# Sheet_Shield.net
KiCad netlist of a schematic drawn in Altium Designer
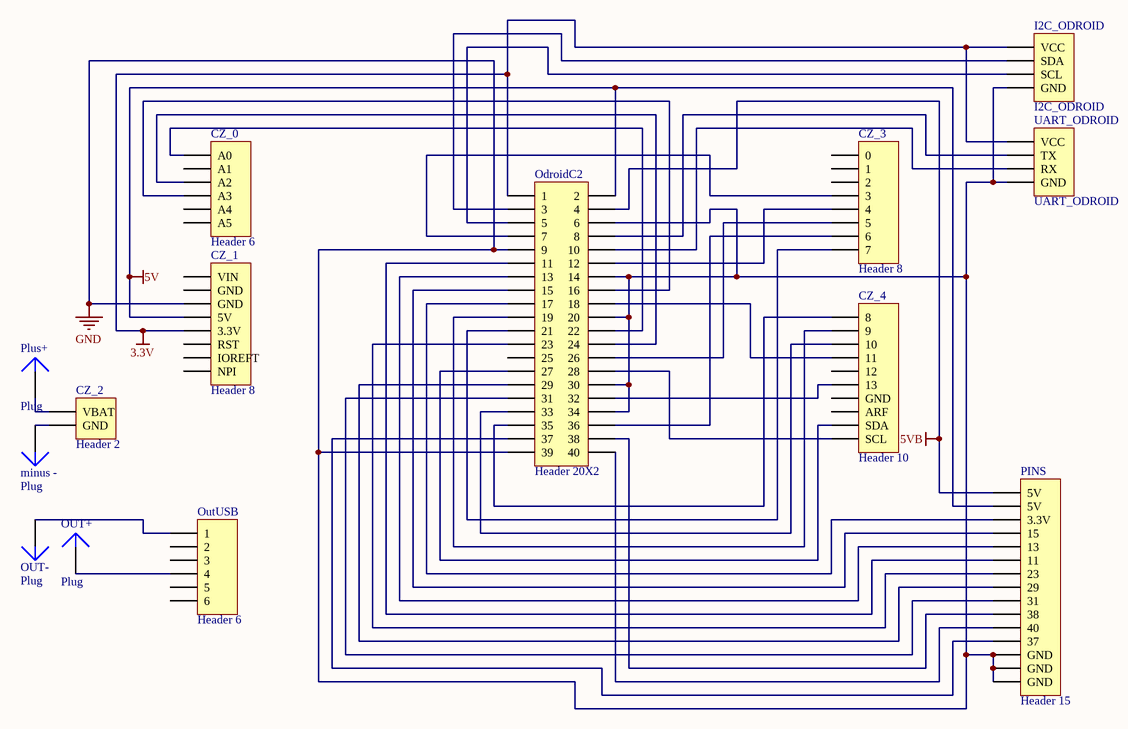
[diagram p0: Sheet_Shield.SchDoc]

(export (version "E")
  (design (tool "Eeschema 10.0.6"))
  (components
    (comp (ref "CZ_0")
      (value "Header 6")
      (footprint "HDR1X6")
      (description "Header, 6-Pin")
      (fields (field (name "PUBLISHER") "Altium Limited"))
      (libsource (lib "Miscellaneous Connectors") (part "Header 6"))
    )
    (comp (ref "CZ_1")
      (value "Header 8")
      (footprint "HDR1X8")
      (description "Header, 8-Pin")
      (fields (field (name "PUBLISHER") "Altium Limited"))
      (libsource (lib "Miscellaneous Connectors") (part "Header 8"))
    )
    (comp (ref "CZ_2")
      (value "Header 2")
      (footprint "HDR1X2")
      (description "Header, 2-Pin")
      (fields (field (name "PUBLISHER") "Altium Limited"))
      (libsource (lib "Miscellaneous Connectors") (part "Header 2"))
    )
    (comp (ref "CZ_3")
      (value "Header 8")
      (footprint "HDR1X8")
      (description "Header, 8-Pin")
      (fields (field (name "PUBLISHER") "Altium Limited"))
      (libsource (lib "Miscellaneous Connectors") (part "Header 8"))
    )
    (comp (ref "CZ_4")
      (value "Header 10")
      (footprint "HDR1X10")
      (description "Header, 10-Pin")
      (fields (field (name "PUBLISHER") "Altium Limited"))
      (libsource (lib "Miscellaneous Connectors") (part "Header 10"))
    )
    (comp (ref "I2C_ODROID")
      (value "I2C_ODROID")
      (footprint "HDR1X4")
      (description "Header, 4-Pin")
      (fields (field (name "PUBLISHER") "Altium Limited"))
      (libsource (lib "Miscellaneous Connectors") (part "Header 4"))
    )
    (comp (ref "minus -")
      (value "Plug")
      (footprint "PIN1")
      (fields (field (name "PUBLISHER") "Altium Limited"))
      (libsource (lib "Miscellaneous Connectors") (part "Plug"))
    )
    (comp (ref "OdroidC2")
      (value "Header 20X2")
      (footprint "HDR2X20")
      (description "Header, 20-Pin, Dual row")
      (fields (field (name "PUBLISHER") "Altium Limited"))
      (libsource (lib "Miscellaneous Connectors") (part "Header 20X2"))
    )
    (comp (ref "OUT+")
      (value "Plug")
      (footprint "PIN1")
      (fields (field (name "PUBLISHER") "Altium Limited"))
      (libsource (lib "Miscellaneous Connectors") (part "Plug"))
    )
    (comp (ref "OUT-")
      (value "Plug")
      (footprint "PIN1")
      (fields (field (name "PUBLISHER") "Altium Limited"))
      (libsource (lib "Miscellaneous Connectors") (part "Plug"))
    )
    (comp (ref "OutUSB")
      (value "Header 6")
      (footprint "USB2.5-2H4C")
      (description "Header, 6-Pin")
      (fields (field (name "PUBLISHER") "Altium Limited"))
      (libsource (lib "") (part "Header 6_1"))
    )
    (comp (ref "PINS")
      (value "Header 15")
      (footprint "HDR1X15")
      (description "Header, 15-Pin")
      (fields (field (name "PUBLISHER") "Altium Limited"))
      (libsource (lib "Miscellaneous Connectors") (part "Header 15"))
    )
    (comp (ref "Plus+")
      (value "Plug")
      (footprint "PIN1")
      (fields (field (name "PUBLISHER") "Altium Limited"))
      (libsource (lib "Miscellaneous Connectors") (part "Plug"))
    )
    (comp (ref "UART_ODROID")
      (value "UART_ODROID")
      (footprint "HDR1X4")
      (description "Header, 4-Pin")
      (fields (field (name "PUBLISHER") "Altium Limited"))
      (libsource (lib "Miscellaneous Connectors") (part "Header 4"))
    )
  )
  (nets
    (net (code "1") (name "3.3V") (class "Default")
      (node (ref "CZ_1") (pin "5") (pinfunction "3.3V_5") (pintype "passive"))
      (node (ref "I2C_ODROID") (pin "1") (pinfunction "VCC_1") (pintype "passive"))
      (node (ref "OdroidC2") (pin "1") (pinfunction "1_1") (pintype "passive"))
      (node (ref "UART_ODROID") (pin "1") (pinfunction "VCC_1") (pintype "passive"))
    )
    (net (code "2") (name "5V") (class "Default")
      (node (ref "CZ_1") (pin "4") (pinfunction "5V_4") (pintype "passive"))
      (node (ref "OdroidC2") (pin "2") (pinfunction "2_2") (pintype "passive"))
      (node (ref "PINS") (pin "2") (pinfunction "5V_2") (pintype "passive"))
    )
    (net (code "3") (name "5VB") (class "Default")
      (node (ref "OdroidC2") (pin "4") (pinfunction "4_4") (pintype "passive"))
      (node (ref "PINS") (pin "1") (pinfunction "5V_1") (pintype "passive"))
    )
    (net (code "4") (name "GND") (class "Default")
      (node (ref "CZ_1") (pin "3") (pinfunction "GND_3") (pintype "passive"))
      (node (ref "I2C_ODROID") (pin "4") (pinfunction "GND_4") (pintype "passive"))
      (node (ref "OdroidC2") (pin "14") (pinfunction "14_14") (pintype "passive"))
      (node (ref "OdroidC2") (pin "20") (pinfunction "20_20") (pintype "passive"))
      (node (ref "OdroidC2") (pin "30") (pinfunction "30_30") (pintype "passive"))
      (node (ref "OdroidC2") (pin "34") (pinfunction "34_34") (pintype "passive"))
      (node (ref "OdroidC2") (pin "39") (pinfunction "39_39") (pintype "passive"))
      (node (ref "OdroidC2") (pin "6") (pinfunction "6_6") (pintype "passive"))
      (node (ref "OdroidC2") (pin "9") (pinfunction "9_9") (pintype "passive"))
      (node (ref "PINS") (pin "13") (pinfunction "GND_13") (pintype "passive"))
      (node (ref "PINS") (pin "14") (pinfunction "GND_14") (pintype "passive"))
      (node (ref "PINS") (pin "15") (pinfunction "GND_15") (pintype "passive"))
      (node (ref "UART_ODROID") (pin "4") (pinfunction "GND_4") (pintype "passive"))
    )
    (net (code "5") (name "Net-(CZ_0-A0)") (class "Default")
      (node (ref "CZ_0") (pin "1") (pinfunction "A0_1") (pintype "passive"))
      (node (ref "OdroidC2") (pin "22") (pinfunction "22_22") (pintype "passive"))
    )
    (net (code "6") (name "Net-(CZ_0-A2)") (class "Default")
      (node (ref "CZ_0") (pin "3") (pinfunction "A2_3") (pintype "passive"))
      (node (ref "OdroidC2") (pin "24") (pinfunction "24_24") (pintype "passive"))
    )
    (net (code "7") (name "Net-(CZ_0-A3)") (class "Default")
      (node (ref "CZ_0") (pin "4") (pinfunction "A3_4") (pintype "passive"))
      (node (ref "OdroidC2") (pin "16") (pinfunction "16_16") (pintype "passive"))
    )
    (net (code "8") (name "Net-(CZ_2-GND)") (class "Default")
      (node (ref "CZ_2") (pin "2") (pinfunction "GND_2") (pintype "passive"))
      (node (ref "minus -") (pin "1") (pinfunction "1_1") (pintype "passive"))
    )
    (net (code "9") (name "Net-(CZ_2-VBAT)") (class "Default")
      (node (ref "CZ_2") (pin "1") (pinfunction "VBAT_1") (pintype "passive"))
      (node (ref "Plus+") (pin "1") (pinfunction "1_1") (pintype "passive"))
    )
    (net (code "10") (name "Net-(CZ_3-3.3V)") (class "Default")
      (node (ref "CZ_3") (pin "5") (pinfunction "3.3V_5") (pintype "passive"))
      (node (ref "OdroidC2") (pin "12") (pinfunction "12_12") (pintype "passive"))
    )
    (net (code "11") (name "Net-(CZ_3-5V)") (class "Default")
      (node (ref "CZ_3") (pin "4") (pinfunction "5V_4") (pintype "passive"))
      (node (ref "OdroidC2") (pin "7") (pinfunction "7_7") (pintype "passive"))
    )
    (net (code "12") (name "Net-(CZ_3-IOREFT)") (class "Default")
      (node (ref "CZ_3") (pin "7") (pinfunction "IOREFT_7") (pintype "passive"))
      (node (ref "OdroidC2") (pin "36") (pinfunction "36_36") (pintype "passive"))
    )
    (net (code "13") (name "Net-(CZ_3-NPI)") (class "Default")
      (node (ref "CZ_3") (pin "8") (pinfunction "NPI_8") (pintype "passive"))
      (node (ref "OdroidC2") (pin "21") (pinfunction "21_21") (pintype "passive"))
    )
    (net (code "14") (name "Net-(CZ_3-RST)") (class "Default")
      (node (ref "CZ_3") (pin "6") (pinfunction "RST_6") (pintype "passive"))
      (node (ref "OdroidC2") (pin "26") (pinfunction "26_26") (pintype "passive"))
    )
    (net (code "15") (name "Net-(CZ_4-8)") (class "Default")
      (node (ref "CZ_4") (pin "1") (pinfunction "8_1") (pintype "passive"))
      (node (ref "OdroidC2") (pin "35") (pinfunction "35_35") (pintype "passive"))
    )
    (net (code "16") (name "Net-(CZ_4-9)") (class "Default")
      (node (ref "CZ_4") (pin "2") (pinfunction "9_2") (pintype "passive"))
      (node (ref "OdroidC2") (pin "19") (pinfunction "19_19") (pintype "passive"))
    )
    (net (code "17") (name "Net-(CZ_4-10)") (class "Default")
      (node (ref "CZ_4") (pin "3") (pinfunction "10_3") (pintype "passive"))
      (node (ref "OdroidC2") (pin "33") (pinfunction "33_33") (pintype "passive"))
    )
    (net (code "18") (name "Net-(CZ_4-11)") (class "Default")
      (node (ref "CZ_4") (pin "4") (pinfunction "11_4") (pintype "passive"))
      (node (ref "OdroidC2") (pin "18") (pinfunction "18_18") (pintype "passive"))
    )
    (net (code "19") (name "Net-(CZ_4-13)") (class "Default")
      (node (ref "CZ_4") (pin "6") (pinfunction "13_6") (pintype "passive"))
      (node (ref "OdroidC2") (pin "32") (pinfunction "32_32") (pintype "passive"))
    )
    (net (code "20") (name "Net-(CZ_4-SCL)") (class "Default")
      (node (ref "CZ_4") (pin "10") (pinfunction "SCL_10") (pintype "passive"))
      (node (ref "OdroidC2") (pin "28") (pinfunction "28_28") (pintype "passive"))
    )
    (net (code "21") (name "Net-(CZ_4-SDA)") (class "Default")
      (node (ref "CZ_4") (pin "9") (pinfunction "SDA_9") (pintype "passive"))
      (node (ref "OdroidC2") (pin "27") (pinfunction "27_27") (pintype "passive"))
    )
    (net (code "22") (name "Net-(I2C_ODROID-SCL)") (class "Default")
      (node (ref "I2C_ODROID") (pin "3") (pinfunction "SCL_3") (pintype "passive"))
      (node (ref "OdroidC2") (pin "5") (pinfunction "5_5") (pintype "passive"))
    )
    (net (code "23") (name "Net-(I2C_ODROID-SDA)") (class "Default")
      (node (ref "I2C_ODROID") (pin "2") (pinfunction "SDA_2") (pintype "passive"))
      (node (ref "OdroidC2") (pin "3") (pinfunction "3_3") (pintype "passive"))
    )
    (net (code "24") (name "Net-(OUT+-Pad1)") (class "Default")
      (node (ref "OUT+") (pin "1") (pinfunction "1_1") (pintype "passive"))
      (node (ref "OutUSB") (pin "4") (pinfunction "4_4") (pintype "passive"))
    )
    (net (code "25") (name "Net-(OUT--Pad1)") (class "Default")
      (node (ref "OUT-") (pin "1") (pinfunction "1_1") (pintype "passive"))
      (node (ref "OutUSB") (pin "1") (pinfunction "1_1") (pintype "passive"))
    )
    (net (code "26") (name "Net-(PINS-3.3V)") (class "Default")
      (node (ref "OdroidC2") (pin "17") (pinfunction "17_17") (pintype "passive"))
      (node (ref "PINS") (pin "3") (pinfunction "3.3V_3") (pintype "passive"))
    )
    (net (code "27") (name "Net-(PINS-11)") (class "Default")
      (node (ref "OdroidC2") (pin "11") (pinfunction "11_11") (pintype "passive"))
      (node (ref "PINS") (pin "6") (pinfunction "11_6") (pintype "passive"))
    )
    (net (code "28") (name "Net-(PINS-13)") (class "Default")
      (node (ref "OdroidC2") (pin "13") (pinfunction "13_13") (pintype "passive"))
      (node (ref "PINS") (pin "5") (pinfunction "13_5") (pintype "passive"))
    )
    (net (code "29") (name "Net-(PINS-15)") (class "Default")
      (node (ref "OdroidC2") (pin "15") (pinfunction "15_15") (pintype "passive"))
      (node (ref "PINS") (pin "4") (pinfunction "15_4") (pintype "passive"))
    )
    (net (code "30") (name "Net-(PINS-23)") (class "Default")
      (node (ref "OdroidC2") (pin "23") (pinfunction "23_23") (pintype "passive"))
      (node (ref "PINS") (pin "7") (pinfunction "23_7") (pintype "passive"))
    )
    (net (code "31") (name "Net-(PINS-29)") (class "Default")
      (node (ref "OdroidC2") (pin "29") (pinfunction "29_29") (pintype "passive"))
      (node (ref "PINS") (pin "8") (pinfunction "29_8") (pintype "passive"))
    )
    (net (code "32") (name "Net-(PINS-31)") (class "Default")
      (node (ref "OdroidC2") (pin "31") (pinfunction "31_31") (pintype "passive"))
      (node (ref "PINS") (pin "9") (pinfunction "31_9") (pintype "passive"))
    )
    (net (code "33") (name "Net-(PINS-37)") (class "Default")
      (node (ref "OdroidC2") (pin "37") (pinfunction "37_37") (pintype "passive"))
      (node (ref "PINS") (pin "12") (pinfunction "37_12") (pintype "passive"))
    )
    (net (code "34") (name "Net-(PINS-38)") (class "Default")
      (node (ref "OdroidC2") (pin "38") (pinfunction "38_38") (pintype "passive"))
      (node (ref "PINS") (pin "10") (pinfunction "38_10") (pintype "passive"))
    )
    (net (code "35") (name "Net-(PINS-40)") (class "Default")
      (node (ref "OdroidC2") (pin "40") (pinfunction "40_40") (pintype "passive"))
      (node (ref "PINS") (pin "11") (pinfunction "40_11") (pintype "passive"))
    )
    (net (code "36") (name "Net-(UART_ODROID-SCL)") (class "Default")
      (node (ref "OdroidC2") (pin "10") (pinfunction "10_10") (pintype "passive"))
      (node (ref "UART_ODROID") (pin "3") (pinfunction "SCL_3") (pintype "passive"))
    )
    (net (code "37") (name "Net-(UART_ODROID-SDA)") (class "Default")
      (node (ref "OdroidC2") (pin "8") (pinfunction "8_8") (pintype "passive"))
      (node (ref "UART_ODROID") (pin "2") (pinfunction "SDA_2") (pintype "passive"))
    )
    (net (code "38") (name "unconnected-(CZ_0-A1-Pad2)") (class "Default")
      (node (ref "CZ_0") (pin "2") (pinfunction "A1_2") (pintype "passive"))
    )
    (net (code "39") (name "unconnected-(CZ_0-A4-Pad5)") (class "Default")
      (node (ref "CZ_0") (pin "5") (pinfunction "A4_5") (pintype "passive"))
    )
    (net (code "40") (name "unconnected-(CZ_0-A5-Pad6)") (class "Default")
      (node (ref "CZ_0") (pin "6") (pinfunction "A5_6") (pintype "passive"))
    )
    (net (code "41") (name "unconnected-(CZ_1-GND-Pad2)") (class "Default")
      (node (ref "CZ_1") (pin "2") (pinfunction "GND_2") (pintype "passive"))
    )
    (net (code "42") (name "unconnected-(CZ_1-IOREFT-Pad7)") (class "Default")
      (node (ref "CZ_1") (pin "7") (pinfunction "IOREFT_7") (pintype "passive"))
    )
    (net (code "43") (name "unconnected-(CZ_1-NPI-Pad8)") (class "Default")
      (node (ref "CZ_1") (pin "8") (pinfunction "NPI_8") (pintype "passive"))
    )
    (net (code "44") (name "unconnected-(CZ_1-RST-Pad6)") (class "Default")
      (node (ref "CZ_1") (pin "6") (pinfunction "RST_6") (pintype "passive"))
    )
    (net (code "45") (name "unconnected-(CZ_1-VIN-Pad1)") (class "Default")
      (node (ref "CZ_1") (pin "1") (pinfunction "VIN_1") (pintype "passive"))
    )
    (net (code "46") (name "unconnected-(CZ_3-GND-Pad2)") (class "Default")
      (node (ref "CZ_3") (pin "2") (pinfunction "GND_2") (pintype "passive"))
    )
    (net (code "47") (name "unconnected-(CZ_3-GND-Pad3)") (class "Default")
      (node (ref "CZ_3") (pin "3") (pinfunction "GND_3") (pintype "passive"))
    )
    (net (code "48") (name "unconnected-(CZ_3-VIN-Pad1)") (class "Default")
      (node (ref "CZ_3") (pin "1") (pinfunction "VIN_1") (pintype "passive"))
    )
    (net (code "49") (name "unconnected-(CZ_4-12-Pad5)") (class "Default")
      (node (ref "CZ_4") (pin "5") (pinfunction "12_5") (pintype "passive"))
    )
    (net (code "50") (name "unconnected-(CZ_4-ARF-Pad8)") (class "Default")
      (node (ref "CZ_4") (pin "8") (pinfunction "ARF_8") (pintype "passive"))
    )
    (net (code "51") (name "unconnected-(CZ_4-GND-Pad7)") (class "Default")
      (node (ref "CZ_4") (pin "7") (pinfunction "GND_7") (pintype "passive"))
    )
    (net (code "52") (name "unconnected-(OdroidC2-Pad25)") (class "Default")
      (node (ref "OdroidC2") (pin "25") (pinfunction "25_25") (pintype "passive"))
    )
    (net (code "53") (name "unconnected-(OutUSB-Pad2)") (class "Default")
      (node (ref "OutUSB") (pin "2") (pinfunction "2_2") (pintype "passive"))
    )
    (net (code "54") (name "unconnected-(OutUSB-Pad3)") (class "Default")
      (node (ref "OutUSB") (pin "3") (pinfunction "3_3") (pintype "passive"))
    )
    (net (code "55") (name "unconnected-(OutUSB-Pad5)") (class "Default")
      (node (ref "OutUSB") (pin "5") (pinfunction "5_5") (pintype "passive"))
    )
    (net (code "56") (name "unconnected-(OutUSB-Pad6)") (class "Default")
      (node (ref "OutUSB") (pin "6") (pinfunction "6_6") (pintype "passive"))
    )
  )
)
